# switching-psu.net
KiCad netlist of a schematic drawn in EAGLE
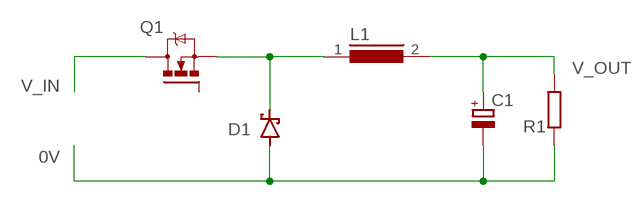
[diagram p0: schematic, sheet 1]

(export (version "E")
  (design (tool "Eeschema 10.0.6"))
  (components
    (comp (ref "C1")
      (value "CPOL-EUE7.5-18")
      (footprint "eagle-import:E7,5-18")
      (libsource (lib "eagle-import") (part "CPOL-EUE7.5-18"))
    )
    (comp (ref "D1")
      (value "1N5819-B")
      (footprint "eagle-import:DO41-7.6")
      (libsource (lib "eagle-import") (part "1N5819-B"))
    )
    (comp (ref "L1")
      (value "A26GFC")
      (footprint "eagle-import:A26GFC")
      (libsource (lib "eagle-import") (part "A26GFC"))
    )
    (comp (ref "Q1")
      (value "IRFZ48Z")
      (footprint "eagle-import:TO220BH")
      (libsource (lib "eagle-import") (part "IRFZ48Z"))
    )
    (comp (ref "R1")
      (value "R-EU_0207/10")
      (footprint "eagle-import:0207_10")
      (libsource (lib "eagle-import") (part "R-EU_0207/10"))
    )
  )
  (nets
    (net (code "1") (name "/0V") (class "Default")
      (node (ref "C1") (pin "-") (pinfunction "-_-") (pintype "passive"))
      (node (ref "D1") (pin "A") (pinfunction "A_A") (pintype "passive"))
      (node (ref "R1") (pin "1") (pinfunction "1_1") (pintype "passive"))
    )
    (net (code "2") (name "/V_IN") (class "Default")
      (node (ref "Q1") (pin "D") (pinfunction "D_D") (pintype "passive"))
    )
    (net (code "3") (name "/V_OUT") (class "Default")
      (node (ref "C1") (pin "+") (pinfunction "+_+") (pintype "passive"))
      (node (ref "L1") (pin "2") (pinfunction "2_2") (pintype "passive"))
      (node (ref "R1") (pin "2") (pinfunction "2_2") (pintype "passive"))
    )
    (net (code "4") (name "Net-(D1-PadC)") (class "Default")
      (node (ref "D1") (pin "C") (pinfunction "C_C") (pintype "passive"))
      (node (ref "L1") (pin "1") (pinfunction "1_1") (pintype "passive"))
      (node (ref "Q1") (pin "S") (pinfunction "S_S") (pintype "passive"))
    )
    (net (code "5") (name "unconnected-(Q1-PadG)") (class "Default")
      (node (ref "Q1") (pin "G") (pinfunction "G_G") (pintype "passive"))
    )
  )
)
